# schematic.net
KiCad netlist of a schematic drawn in Altium Designer
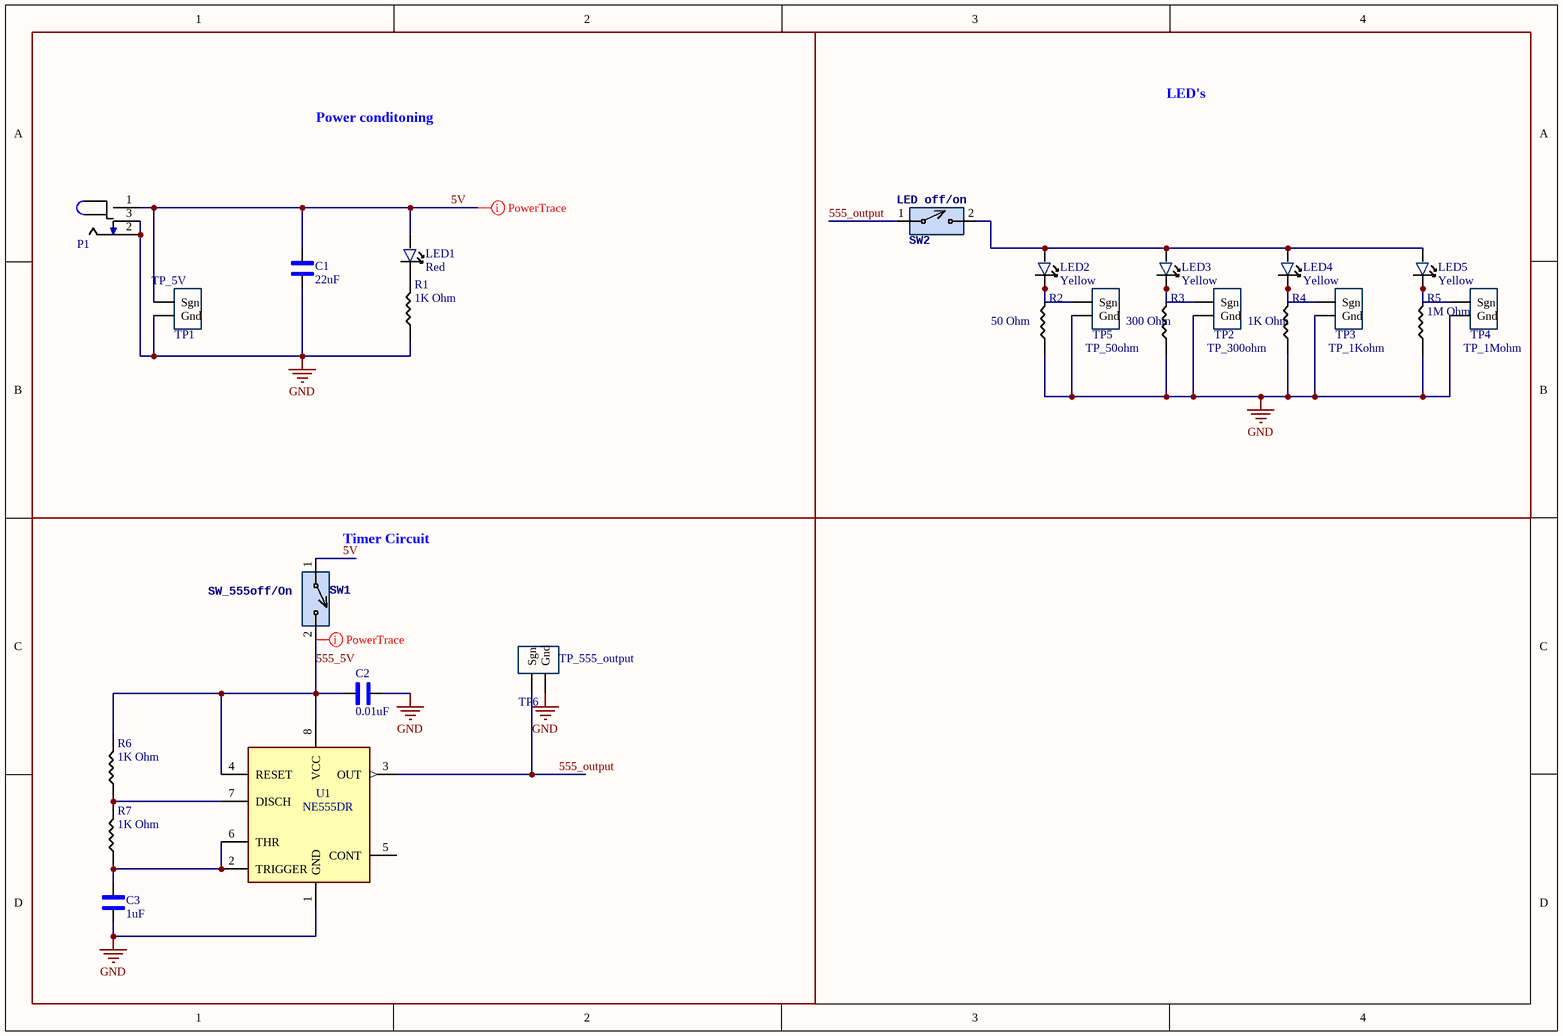
[diagram p0: schematic.SchDoc]

(export (version "E")
  (design (tool "Eeschema 10.0.6"))
  (components
    (comp (ref "C1")
      (value "22uF")
      (footprint "1206_Passive_Capacitor")
      (description "22uF ±10% 25V X5R 1206 Multilayer Ceramic Capacitors MLCC - SMD/SMT RoHS")
      (fields (field (name "MFR PART #") "CL31A226KAHNNNE") (field (name "LCSC PART#") "C12891"))
      (libsource (lib "ECEN5730Lib_2023_05_DS") (part "C_22uF_1206"))
    )
    (comp (ref "C2")
      (value "0.01uF")
      (footprint "1206_Passive_Capacitor")
      (description "MULTILAYER CERAMIC CAPACITORS MLCC - SMD/SMT 1UF 50V 1206 ROHS")
      (fields (field (name "MFR PART #") "CL31B105KBHNNNE") (field (name "LCSC PART#") "C1848"))
      (libsource (lib "ECEN5730Lib_2023_05_DS") (part "C_1uF_1206"))
    )
    (comp (ref "C3")
      (value "1uF")
      (footprint "1206_Passive_Capacitor")
      (description "MULTILAYER CERAMIC CAPACITORS MLCC - SMD/SMT 1UF 50V 1206 ROHS")
      (fields (field (name "MFR PART #") "CL31B105KBHNNNE") (field (name "LCSC PART#") "C1848"))
      (libsource (lib "ECEN5730Lib_2023_05_DS") (part "C_1uF_1206"))
    )
    (comp (ref "LED1")
      (value "Red")
      (footprint "LED_1206")
      (description "Red 621~631nm 1206 Light Emitting Diodes (LED) RoHS")
      (fields (field (name "MFR PART #") "15-21/R6C-FQ1R1B/2T") (field (name "LCSC PART#") "C93133"))
      (libsource (lib "ECEN5730Lib_2023_05_DS") (part "LED_RED_1206"))
    )
    (comp (ref "LED2")
      (value "Yellow")
      (footprint "LED_1206")
      (description "yellow 1206  Light Emitting Diodes (LED) ROHS")
      (fields (field (name "LCSC PART#") "C93094") (field (name "MFR PART #") "NCD1206Y1"))
      (libsource (lib "ECEN5730Lib_2023_05_DS") (part "LED_YELLOW_1206"))
    )
    (comp (ref "LED3")
      (value "Yellow")
      (footprint "LED_1206")
      (description "yellow 1206  Light Emitting Diodes (LED) ROHS")
      (fields (field (name "LCSC PART#") "C93094") (field (name "MFR PART #") "NCD1206Y1"))
      (libsource (lib "ECEN5730Lib_2023_05_DS") (part "LED_YELLOW_1206"))
    )
    (comp (ref "LED4")
      (value "Yellow")
      (footprint "LED_1206")
      (description "yellow 1206  Light Emitting Diodes (LED) ROHS")
      (fields (field (name "LCSC PART#") "C93094") (field (name "MFR PART #") "NCD1206Y1"))
      (libsource (lib "ECEN5730Lib_2023_05_DS") (part "LED_YELLOW_1206"))
    )
    (comp (ref "LED5")
      (value "Yellow")
      (footprint "LED_1206")
      (description "yellow 1206  Light Emitting Diodes (LED) ROHS")
      (fields (field (name "LCSC PART#") "C93094") (field (name "MFR PART #") "NCD1206Y1"))
      (libsource (lib "ECEN5730Lib_2023_05_DS") (part "LED_YELLOW_1206"))
    )
    (comp (ref "P1")
      (value "Power Jack")
      (footprint "Power_Jack")
      (description "Power Barrel Connector Jack 2.10mm ID (0.083\"), 5.50mm OD (0.217\") Through Hole, Right Angle")
      (fields (field (name "MFR PART #") "PJ-102A") (field (name "LCSC PART#") "C136744"))
      (libsource (lib "ECEN5730Lib_2023_05_DS") (part "P_Power Jack"))
    )
    (comp (ref "R1")
      (value "1K Ohm")
      (footprint "1206_Passive_Resitor")
      (description "CHIP RESISTOR - SURFACE MOUNT 1KOHMS ±1% 1/4W 1206 ROHS")
      (fields (field (name "MFR PART #") "RNCP1206FTD1K00CT") (field (name "LCSC PART#") "C4410"))
      (libsource (lib "ECEN5730Lib_2023_05_DS") (part "R_1K_1206"))
    )
    (comp (ref "R2")
      (value "50 Ohm")
      (footprint "1206_Passive_Resitor")
      (description "CHIP RESISTOR - SURFACE MOUNT 1KOHMS ±1% 1/4W 1206 ROHS")
      (fields (field (name "MFR PART #") "RNCP1206FTD1K00CT") (field (name "LCSC PART#") "C4410"))
      (libsource (lib "ECEN5730Lib_2023_05_DS") (part "R_1K_1206"))
    )
    (comp (ref "R3")
      (value "300 Ohm")
      (footprint "1206_Passive_Resitor")
      (description "CHIP RESISTOR - SURFACE MOUNT 1KOHMS ±1% 1/4W 1206 ROHS")
      (fields (field (name "MFR PART #") "RNCP1206FTD1K00CT") (field (name "LCSC PART#") "C4410"))
      (libsource (lib "ECEN5730Lib_2023_05_DS") (part "R_1K_1206"))
    )
    (comp (ref "R4")
      (value "1K Ohm")
      (footprint "1206_Passive_Resitor")
      (description "CHIP RESISTOR - SURFACE MOUNT 1KOHMS ±1% 1/4W 1206 ROHS")
      (fields (field (name "MFR PART #") "RNCP1206FTD1K00CT") (field (name "LCSC PART#") "C4410"))
      (libsource (lib "ECEN5730Lib_2023_05_DS") (part "R_1K_1206"))
    )
    (comp (ref "R5")
      (value "1M Ohm")
      (footprint "1206_Passive_Resitor")
      (description "CHIP RESISTOR - SURFACE MOUNT 1KOHMS ±1% 1/4W 1206 ROHS")
      (fields (field (name "MFR PART #") "RNCP1206FTD1K00CT") (field (name "LCSC PART#") "C4410"))
      (libsource (lib "ECEN5730Lib_2023_05_DS") (part "R_1K_1206"))
    )
    (comp (ref "R6")
      (value "1K Ohm")
      (footprint "1206_Passive_Resitor")
      (description "CHIP RESISTOR - SURFACE MOUNT 1KOHMS ±1% 1/4W 1206 ROHS")
      (fields (field (name "MFR PART #") "RNCP1206FTD1K00CT") (field (name "LCSC PART#") "C4410"))
      (libsource (lib "ECEN5730Lib_2023_05_DS") (part "R_1K_1206"))
    )
    (comp (ref "R7")
      (value "1K Ohm")
      (footprint "1206_Passive_Resitor")
      (description "CHIP RESISTOR - SURFACE MOUNT 1KOHMS ±1% 1/4W 1206 ROHS")
      (fields (field (name "MFR PART #") "RNCP1206FTD1K00CT") (field (name "LCSC PART#") "C4410"))
      (libsource (lib "ECEN5730Lib_2023_05_DS") (part "R_1K_1206"))
    )
    (comp (ref "SW1")
      (value "SW_555off/On")
      (footprint "2Pin-Header-Conn")
      (description "2Pin Header")
      (fields (field (name "LCSC PART#") "C124375"))
      (libsource (lib "ECEN5730Lib_2023_05_DS") (part "SW_2Pin_100mil_Switch"))
    )
    (comp (ref "SW2")
      (value "LED off/on")
      (footprint "2Pin-Header-Conn")
      (description "2Pin Header")
      (fields (field (name "LCSC PART#") "C124375"))
      (libsource (lib "") (part "SW_2Pin_100mil_Switch_1"))
    )
    (comp (ref "TP1")
      (value "TP_5V")
      (footprint "TP10x_Probe")
      (description "Test Point 300 mil centers")
      (libsource (lib "") (part "TP_10x_Probe_1"))
    )
    (comp (ref "TP2")
      (value "TP_300ohm")
      (footprint "TP10x_Probe")
      (description "Test Point 300 mil centers")
      (libsource (lib "") (part "TP_10x_Probe_1"))
    )
    (comp (ref "TP3")
      (value "TP_1Kohm")
      (footprint "TP10x_Probe")
      (description "Test Point 300 mil centers")
      (libsource (lib "") (part "TP_10x_Probe_1"))
    )
    (comp (ref "TP4")
      (value "TP_1Mohm")
      (footprint "TP10x_Probe")
      (description "Test Point 300 mil centers")
      (libsource (lib "") (part "TP_10x_Probe_1"))
    )
    (comp (ref "TP5")
      (value "TP_50ohm")
      (footprint "TP10x_Probe")
      (description "Test Point 300 mil centers")
      (libsource (lib "") (part "TP_10x_Probe_1"))
    )
    (comp (ref "TP6")
      (value "TP_555_output")
      (footprint "TP10x_Probe")
      (description "Test Point 300 mil centers")
      (libsource (lib "ECEN5730Lib_2023_05_DS") (part "TP_10x_Probe"))
    )
    (comp (ref "U1")
      (value "NE555DR")
      (footprint "TS555IDTTR")
      (description "555 Timer SOIC-8_150MIL ROHS 150ns Rise Time")
      (fields (field (name "LCSC PART#") "C7593"))
      (libsource (lib "ECEN5730Lib_2023_05_DS") (part "U_555_Slow"))
    )
  )
  (nets
    (net (code "1") (name "/5V") (class "Default")
      (node (ref "C1") (pin "2") (pinfunction "2_2") (pintype "passive"))
      (node (ref "LED1") (pin "1") (pinfunction "1_1") (pintype "passive"))
      (node (ref "P1") (pin "1") (pinfunction "1_1") (pintype "power_in"))
      (node (ref "SW1") (pin "1") (pinfunction "1_1") (pintype "passive"))
      (node (ref "TP1") (pin "1") (pinfunction "Sgn_1") (pintype "passive"))
    )
    (net (code "2") (name "/555_5V") (class "Default")
      (node (ref "C2") (pin "2") (pinfunction "2_2") (pintype "passive"))
      (node (ref "R6") (pin "2") (pinfunction "2_2") (pintype "passive"))
      (node (ref "SW1") (pin "2") (pinfunction "2_2") (pintype "passive"))
      (node (ref "U1") (pin "4") (pinfunction "RESET_4") (pintype "passive"))
      (node (ref "U1") (pin "8") (pinfunction "VCC_8") (pintype "power_in"))
    )
    (net (code "3") (name "/555_output") (class "Default")
      (node (ref "SW2") (pin "1") (pinfunction "1_1") (pintype "passive"))
      (node (ref "TP6") (pin "1") (pinfunction "Sgn_1") (pintype "passive"))
      (node (ref "U1") (pin "3") (pinfunction "OUT_3") (pintype "output"))
    )
    (net (code "4") (name "GND") (class "Default")
      (node (ref "C1") (pin "1") (pinfunction "1_1") (pintype "passive"))
      (node (ref "C2") (pin "1") (pinfunction "1_1") (pintype "passive"))
      (node (ref "C3") (pin "2") (pinfunction "2_2") (pintype "passive"))
      (node (ref "P1") (pin "2") (pinfunction "2_2") (pintype "power_in"))
      (node (ref "P1") (pin "3") (pinfunction "3_3") (pintype "power_in"))
      (node (ref "R1") (pin "1") (pinfunction "1_1") (pintype "passive"))
      (node (ref "R2") (pin "1") (pinfunction "1_1") (pintype "passive"))
      (node (ref "R3") (pin "1") (pinfunction "1_1") (pintype "passive"))
      (node (ref "R4") (pin "1") (pinfunction "1_1") (pintype "passive"))
      (node (ref "R5") (pin "1") (pinfunction "1_1") (pintype "passive"))
      (node (ref "TP1") (pin "2") (pinfunction "Gnd_2") (pintype "passive"))
      (node (ref "TP2") (pin "2") (pinfunction "Gnd_2") (pintype "passive"))
      (node (ref "TP3") (pin "2") (pinfunction "Gnd_2") (pintype "passive"))
      (node (ref "TP4") (pin "2") (pinfunction "Gnd_2") (pintype "passive"))
      (node (ref "TP5") (pin "2") (pinfunction "Gnd_2") (pintype "passive"))
      (node (ref "TP6") (pin "2") (pinfunction "Gnd_2") (pintype "passive"))
      (node (ref "U1") (pin "1") (pinfunction "GND_1") (pintype "power_in"))
    )
    (net (code "5") (name "Net-(LED1-Pad2)") (class "Default")
      (node (ref "LED1") (pin "2") (pinfunction "2_2") (pintype "passive"))
      (node (ref "R1") (pin "2") (pinfunction "2_2") (pintype "passive"))
    )
    (net (code "6") (name "Net-(LED2-Pad1)") (class "Default")
      (node (ref "LED2") (pin "1") (pinfunction "1_1") (pintype "passive"))
      (node (ref "LED3") (pin "1") (pinfunction "1_1") (pintype "passive"))
      (node (ref "LED4") (pin "1") (pinfunction "1_1") (pintype "passive"))
      (node (ref "LED5") (pin "1") (pinfunction "1_1") (pintype "passive"))
      (node (ref "SW2") (pin "2") (pinfunction "2_2") (pintype "passive"))
    )
    (net (code "7") (name "Net-(TP2-Sgn)") (class "Default")
      (node (ref "LED3") (pin "2") (pinfunction "2_2") (pintype "passive"))
      (node (ref "R3") (pin "2") (pinfunction "2_2") (pintype "passive"))
      (node (ref "TP2") (pin "1") (pinfunction "Sgn_1") (pintype "passive"))
    )
    (net (code "8") (name "Net-(TP3-Sgn)") (class "Default")
      (node (ref "LED4") (pin "2") (pinfunction "2_2") (pintype "passive"))
      (node (ref "R4") (pin "2") (pinfunction "2_2") (pintype "passive"))
      (node (ref "TP3") (pin "1") (pinfunction "Sgn_1") (pintype "passive"))
    )
    (net (code "9") (name "Net-(TP4-Sgn)") (class "Default")
      (node (ref "LED5") (pin "2") (pinfunction "2_2") (pintype "passive"))
      (node (ref "R5") (pin "2") (pinfunction "2_2") (pintype "passive"))
      (node (ref "TP4") (pin "1") (pinfunction "Sgn_1") (pintype "passive"))
    )
    (net (code "10") (name "Net-(TP5-Sgn)") (class "Default")
      (node (ref "LED2") (pin "2") (pinfunction "2_2") (pintype "passive"))
      (node (ref "R2") (pin "2") (pinfunction "2_2") (pintype "passive"))
      (node (ref "TP5") (pin "1") (pinfunction "Sgn_1") (pintype "passive"))
    )
    (net (code "11") (name "Net-(U1-DISCH)") (class "Default")
      (node (ref "R6") (pin "1") (pinfunction "1_1") (pintype "passive"))
      (node (ref "R7") (pin "2") (pinfunction "2_2") (pintype "passive"))
      (node (ref "U1") (pin "7") (pinfunction "DISCH_7") (pintype "passive"))
    )
    (net (code "12") (name "Net-(U1-THR)") (class "Default")
      (node (ref "C3") (pin "1") (pinfunction "1_1") (pintype "passive"))
      (node (ref "R7") (pin "1") (pinfunction "1_1") (pintype "passive"))
      (node (ref "U1") (pin "2") (pinfunction "TRIGGER_2") (pintype "passive"))
      (node (ref "U1") (pin "6") (pinfunction "THR_6") (pintype "passive"))
    )
    (net (code "13") (name "unconnected-(U1-CONT-Pad5)") (class "Default")
      (node (ref "U1") (pin "5") (pinfunction "CONT_5") (pintype "passive"))
    )
  )
)
